# clock_pow.net
KiCad netlist of a schematic drawn in Altium Designer
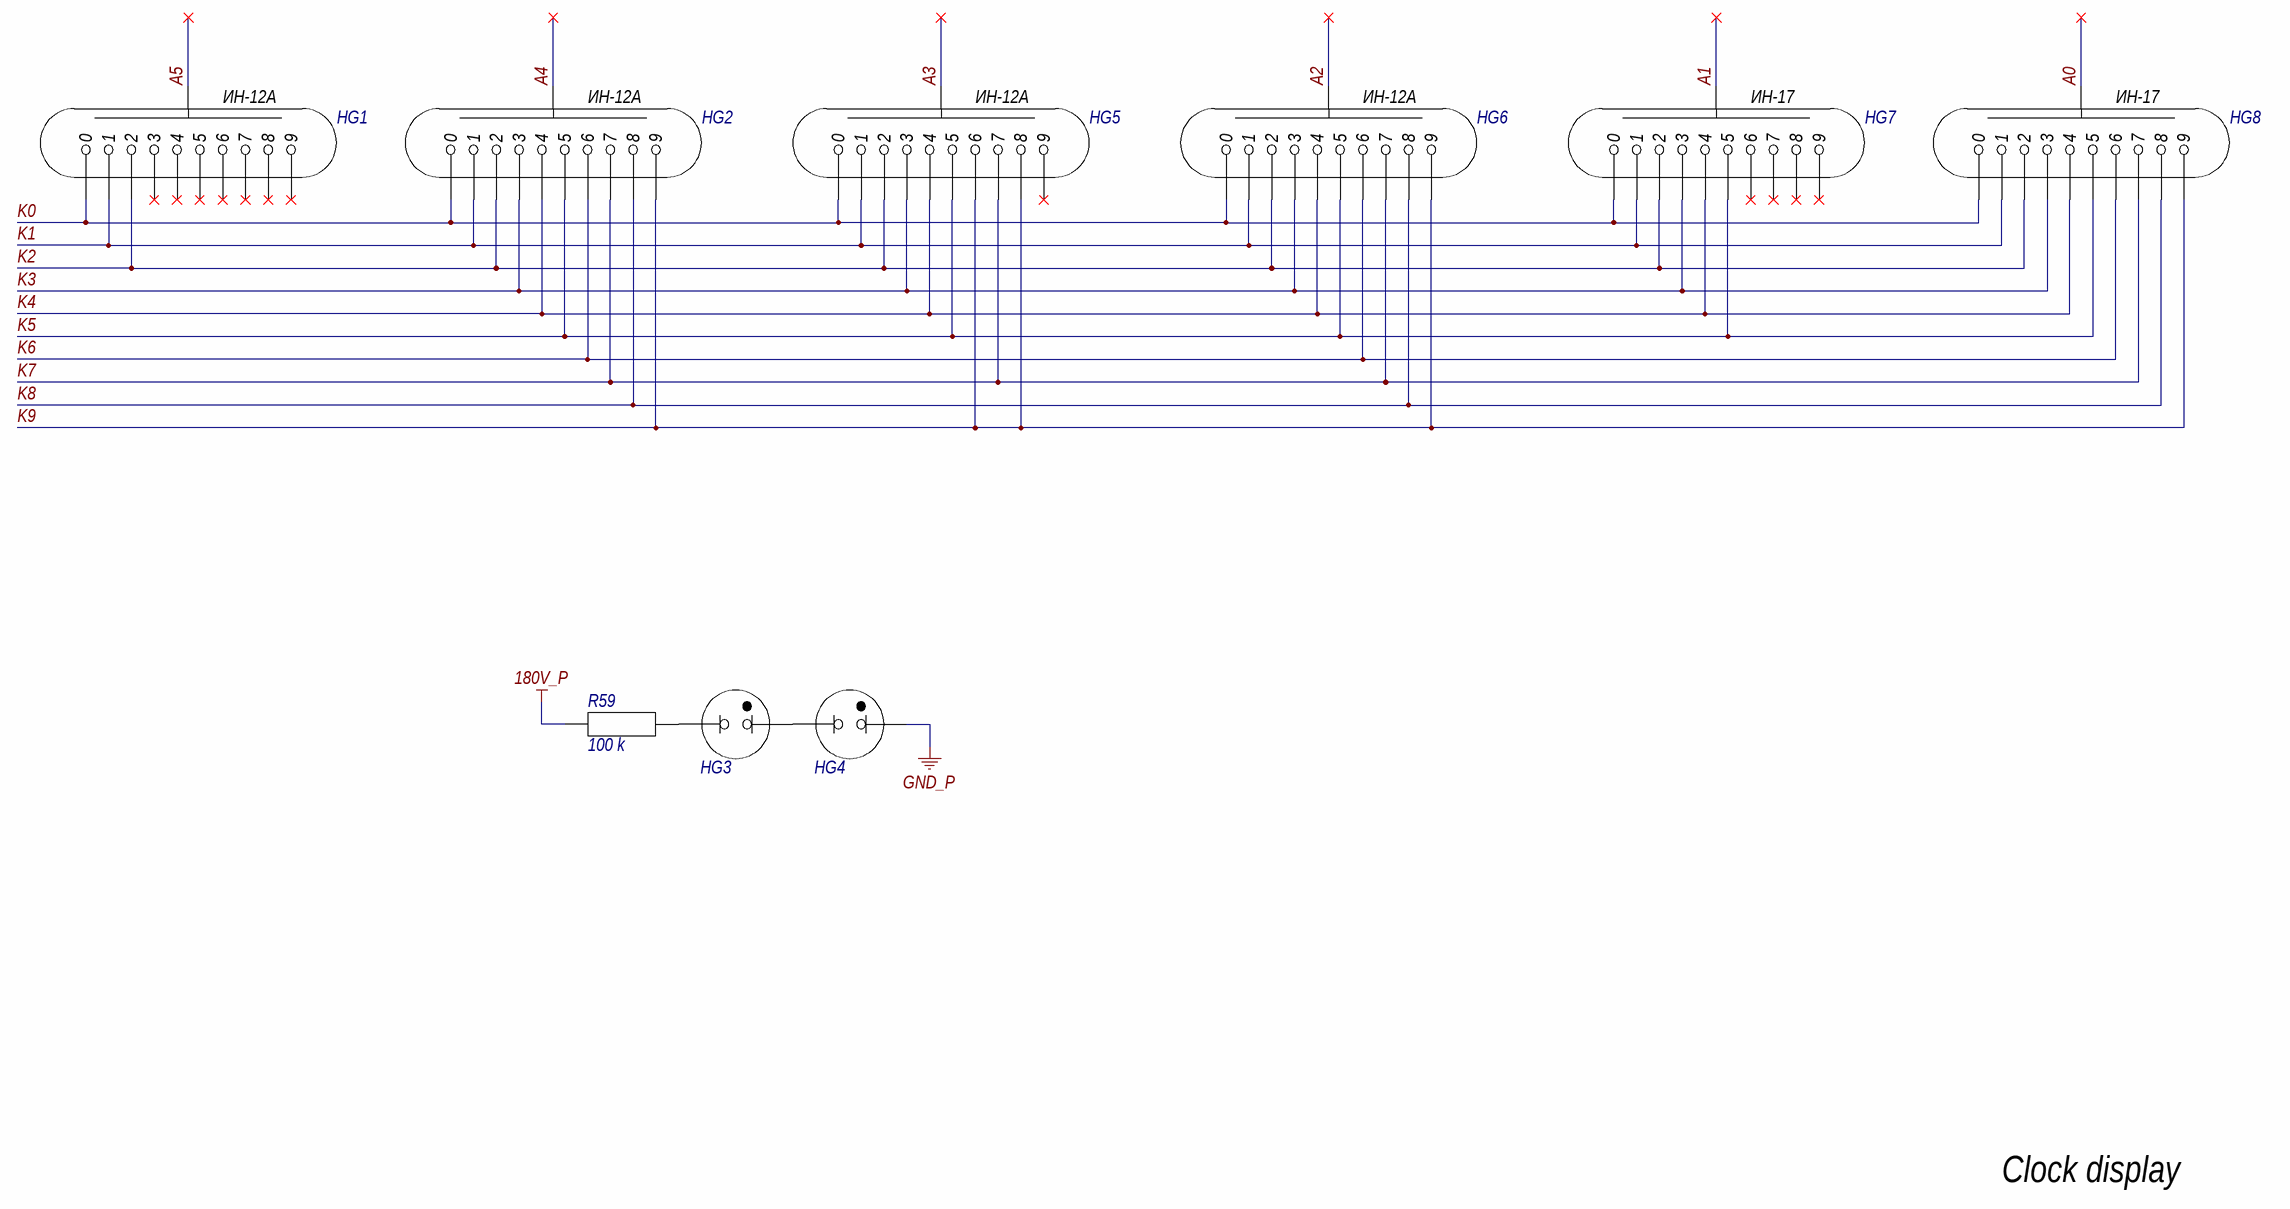
[diagram p0: clock_pow.SchDoc]

(export (version "E")
  (design (tool "Eeschema 10.0.6"))
  (components
    (comp (ref "HG1") (value "ИН-12") (footprint "IN-12-NO-SOKET") (libsource (lib "Schlib1") (part "ИН-12")))
    (comp (ref "HG2") (value "ИН-12") (footprint "IN-12-NO-SOKET") (libsource (lib "Schlib1") (part "ИН-12")))
    (comp (ref "HG3")
      (value "ИНА_ТН_02")
      (footprint "INA_TN_02")
      (libsource (lib "Schlib1") (part "ИНА_ТН_02"))
    )
    (comp (ref "HG4")
      (value "ИНА_ТН_02")
      (footprint "INA_TN_02")
      (libsource (lib "Schlib1") (part "ИНА_ТН_02"))
    )
    (comp (ref "HG5") (value "ИН-12") (footprint "IN-12-NO-SOKET") (libsource (lib "Schlib1") (part "ИН-12")))
    (comp (ref "HG6") (value "ИН-12") (footprint "IN-12-NO-SOKET") (libsource (lib "Schlib1") (part "ИН-12")))
    (comp (ref "HG7") (value "ИН-17") (footprint "IN-17") (libsource (lib "Schlib1") (part "ИН-17")))
    (comp (ref "HG8") (value "ИН-17") (footprint "IN-17") (libsource (lib "Schlib1") (part "ИН-17")))
    (comp (ref "R59")
      (value "100 k")
      (footprint "RES-DIP")
      (fields (field (name "Comment") "R"))
      (libsource (lib "Schlib1") (part "R"))
    )
  )
  (nets
    (net (code "1") (name "/A0") (class "Default")
      (node (ref "HG8") (pin "1") (pinfunction "12_1") (pintype "passive+no_connect"))
    )
    (net (code "2") (name "/A1") (class "Default")
      (node (ref "HG7") (pin "1") (pinfunction "12_1") (pintype "passive+no_connect"))
    )
    (net (code "3") (name "/A2") (class "Default")
      (node (ref "HG6") (pin "1") (pinfunction "12_1") (pintype "passive+no_connect"))
    )
    (net (code "4") (name "/A3") (class "Default")
      (node (ref "HG5") (pin "1") (pinfunction "12_1") (pintype "passive+no_connect"))
    )
    (net (code "5") (name "/A4") (class "Default")
      (node (ref "HG2") (pin "1") (pinfunction "12_1") (pintype "passive+no_connect"))
    )
    (net (code "6") (name "/A5") (class "Default")
      (node (ref "HG1") (pin "1") (pinfunction "12_1") (pintype "passive+no_connect"))
    )
    (net (code "7") (name "/K0") (class "Default")
      (node (ref "HG1") (pin "2") (pinfunction "0_2") (pintype "passive"))
      (node (ref "HG2") (pin "2") (pinfunction "0_2") (pintype "passive"))
      (node (ref "HG5") (pin "2") (pinfunction "0_2") (pintype "passive"))
      (node (ref "HG6") (pin "2") (pinfunction "0_2") (pintype "passive"))
      (node (ref "HG7") (pin "2") (pinfunction "0_2") (pintype "passive"))
      (node (ref "HG8") (pin "2") (pinfunction "0_2") (pintype "passive"))
    )
    (net (code "8") (name "/K1") (class "Default")
      (node (ref "HG1") (pin "11") (pinfunction "1_11") (pintype "passive"))
      (node (ref "HG2") (pin "11") (pinfunction "1_11") (pintype "passive"))
      (node (ref "HG5") (pin "11") (pinfunction "1_11") (pintype "passive"))
      (node (ref "HG6") (pin "11") (pinfunction "1_11") (pintype "passive"))
      (node (ref "HG7") (pin "3") (pinfunction "1_3") (pintype "passive"))
      (node (ref "HG8") (pin "3") (pinfunction "1_3") (pintype "passive"))
    )
    (net (code "9") (name "/K2") (class "Default")
      (node (ref "HG1") (pin "10") (pinfunction "2_10") (pintype "passive"))
      (node (ref "HG2") (pin "10") (pinfunction "2_10") (pintype "passive"))
      (node (ref "HG5") (pin "10") (pinfunction "2_10") (pintype "passive"))
      (node (ref "HG6") (pin "10") (pinfunction "2_10") (pintype "passive"))
      (node (ref "HG7") (pin "4") (pinfunction "2_4") (pintype "passive"))
      (node (ref "HG8") (pin "4") (pinfunction "2_4") (pintype "passive"))
    )
    (net (code "10") (name "/K3") (class "Default")
      (node (ref "HG2") (pin "9") (pinfunction "3_9") (pintype "passive"))
      (node (ref "HG5") (pin "9") (pinfunction "3_9") (pintype "passive"))
      (node (ref "HG6") (pin "9") (pinfunction "3_9") (pintype "passive"))
      (node (ref "HG7") (pin "5") (pinfunction "3_5") (pintype "passive"))
      (node (ref "HG8") (pin "5") (pinfunction "3_5") (pintype "passive"))
    )
    (net (code "11") (name "/K4") (class "Default")
      (node (ref "HG2") (pin "8") (pinfunction "4_8") (pintype "passive"))
      (node (ref "HG5") (pin "8") (pinfunction "4_8") (pintype "passive"))
      (node (ref "HG6") (pin "8") (pinfunction "4_8") (pintype "passive"))
      (node (ref "HG7") (pin "6") (pinfunction "4_6") (pintype "passive"))
      (node (ref "HG8") (pin "6") (pinfunction "4_6") (pintype "passive"))
    )
    (net (code "12") (name "/K5") (class "Default")
      (node (ref "HG2") (pin "7") (pinfunction "5_7") (pintype "passive"))
      (node (ref "HG5") (pin "7") (pinfunction "5_7") (pintype "passive"))
      (node (ref "HG6") (pin "7") (pinfunction "5_7") (pintype "passive"))
      (node (ref "HG7") (pin "7") (pinfunction "5_7") (pintype "passive"))
      (node (ref "HG8") (pin "7") (pinfunction "5_7") (pintype "passive"))
    )
    (net (code "13") (name "/K6") (class "Default")
      (node (ref "HG2") (pin "6") (pinfunction "6_6") (pintype "passive"))
      (node (ref "HG6") (pin "6") (pinfunction "6_6") (pintype "passive"))
      (node (ref "HG8") (pin "8") (pinfunction "6_8") (pintype "passive"))
    )
    (net (code "14") (name "/K7") (class "Default")
      (node (ref "HG2") (pin "5") (pinfunction "7_5") (pintype "passive"))
      (node (ref "HG5") (pin "5") (pinfunction "7_5") (pintype "passive"))
      (node (ref "HG6") (pin "5") (pinfunction "7_5") (pintype "passive"))
      (node (ref "HG8") (pin "9") (pinfunction "7_9") (pintype "passive"))
    )
    (net (code "15") (name "/K8") (class "Default")
      (node (ref "HG2") (pin "4") (pinfunction "8_4") (pintype "passive"))
      (node (ref "HG6") (pin "4") (pinfunction "8_4") (pintype "passive"))
      (node (ref "HG8") (pin "10") (pinfunction "8_10") (pintype "passive"))
    )
    (net (code "16") (name "/K9") (class "Default")
      (node (ref "HG2") (pin "3") (pinfunction "9_3") (pintype "passive"))
      (node (ref "HG5") (pin "4") (pinfunction "8_4") (pintype "passive"))
      (node (ref "HG5") (pin "6") (pinfunction "6_6") (pintype "passive"))
      (node (ref "HG6") (pin "3") (pinfunction "9_3") (pintype "passive"))
      (node (ref "HG8") (pin "11") (pinfunction "9_11") (pintype "passive"))
    )
    (net (code "17") (name "180V_P") (class "Default")
      (node (ref "R59") (pin "1") (pinfunction "1_1") (pintype "passive"))
    )
    (net (code "18") (name "GND_P") (class "Default")
      (node (ref "HG4") (pin "2") (pinfunction "K_2") (pintype "passive"))
    )
    (net (code "19") (name "Net-(HG3-A)") (class "Default")
      (node (ref "HG3") (pin "1") (pinfunction "A_1") (pintype "passive"))
      (node (ref "R59") (pin "2") (pinfunction "2_2") (pintype "passive"))
    )
    (net (code "20") (name "Net-(HG3-K)") (class "Default")
      (node (ref "HG3") (pin "2") (pinfunction "K_2") (pintype "passive"))
      (node (ref "HG4") (pin "1") (pinfunction "A_1") (pintype "passive"))
    )
    (net (code "21") (name "unconnected-(HG1-3-Pad9)") (class "Default")
      (node (ref "HG1") (pin "9") (pinfunction "3_9") (pintype "passive+no_connect"))
    )
    (net (code "22") (name "unconnected-(HG1-4-Pad8)") (class "Default")
      (node (ref "HG1") (pin "8") (pinfunction "4_8") (pintype "passive+no_connect"))
    )
    (net (code "23") (name "unconnected-(HG1-5-Pad7)") (class "Default")
      (node (ref "HG1") (pin "7") (pinfunction "5_7") (pintype "passive+no_connect"))
    )
    (net (code "24") (name "unconnected-(HG1-7-Pad5)") (class "Default")
      (node (ref "HG1") (pin "5") (pinfunction "7_5") (pintype "passive+no_connect"))
    )
    (net (code "25") (name "unconnected-(HG1-8-Pad4)") (class "Default")
      (node (ref "HG1") (pin "4") (pinfunction "8_4") (pintype "passive+no_connect"))
    )
    (net (code "26") (name "unconnected-(HG1-9-Pad3)") (class "Default")
      (node (ref "HG1") (pin "3") (pinfunction "9_3") (pintype "passive+no_connect"))
    )
    (net (code "27") (name "unconnected-(HG1-Pad6)") (class "Default")
      (node (ref "HG1") (pin "6") (pinfunction "6_6") (pintype "passive+no_connect"))
    )
    (net (code "28") (name "unconnected-(HG5-9-Pad3)") (class "Default")
      (node (ref "HG5") (pin "3") (pinfunction "9_3") (pintype "passive+no_connect"))
    )
    (net (code "29") (name "unconnected-(HG7-6-Pad8)") (class "Default")
      (node (ref "HG7") (pin "8") (pinfunction "6_8") (pintype "passive+no_connect"))
    )
    (net (code "30") (name "unconnected-(HG7-7-Pad9)") (class "Default")
      (node (ref "HG7") (pin "9") (pinfunction "7_9") (pintype "passive+no_connect"))
    )
    (net (code "31") (name "unconnected-(HG7-8-Pad10)") (class "Default")
      (node (ref "HG7") (pin "10") (pinfunction "8_10") (pintype "passive+no_connect"))
    )
    (net (code "32") (name "unconnected-(HG7-9-Pad11)") (class "Default")
      (node (ref "HG7") (pin "11") (pinfunction "9_11") (pintype "passive+no_connect"))
    )
  )
)
